# Sheet1.net
KiCad netlist of a schematic drawn in Altium Designer
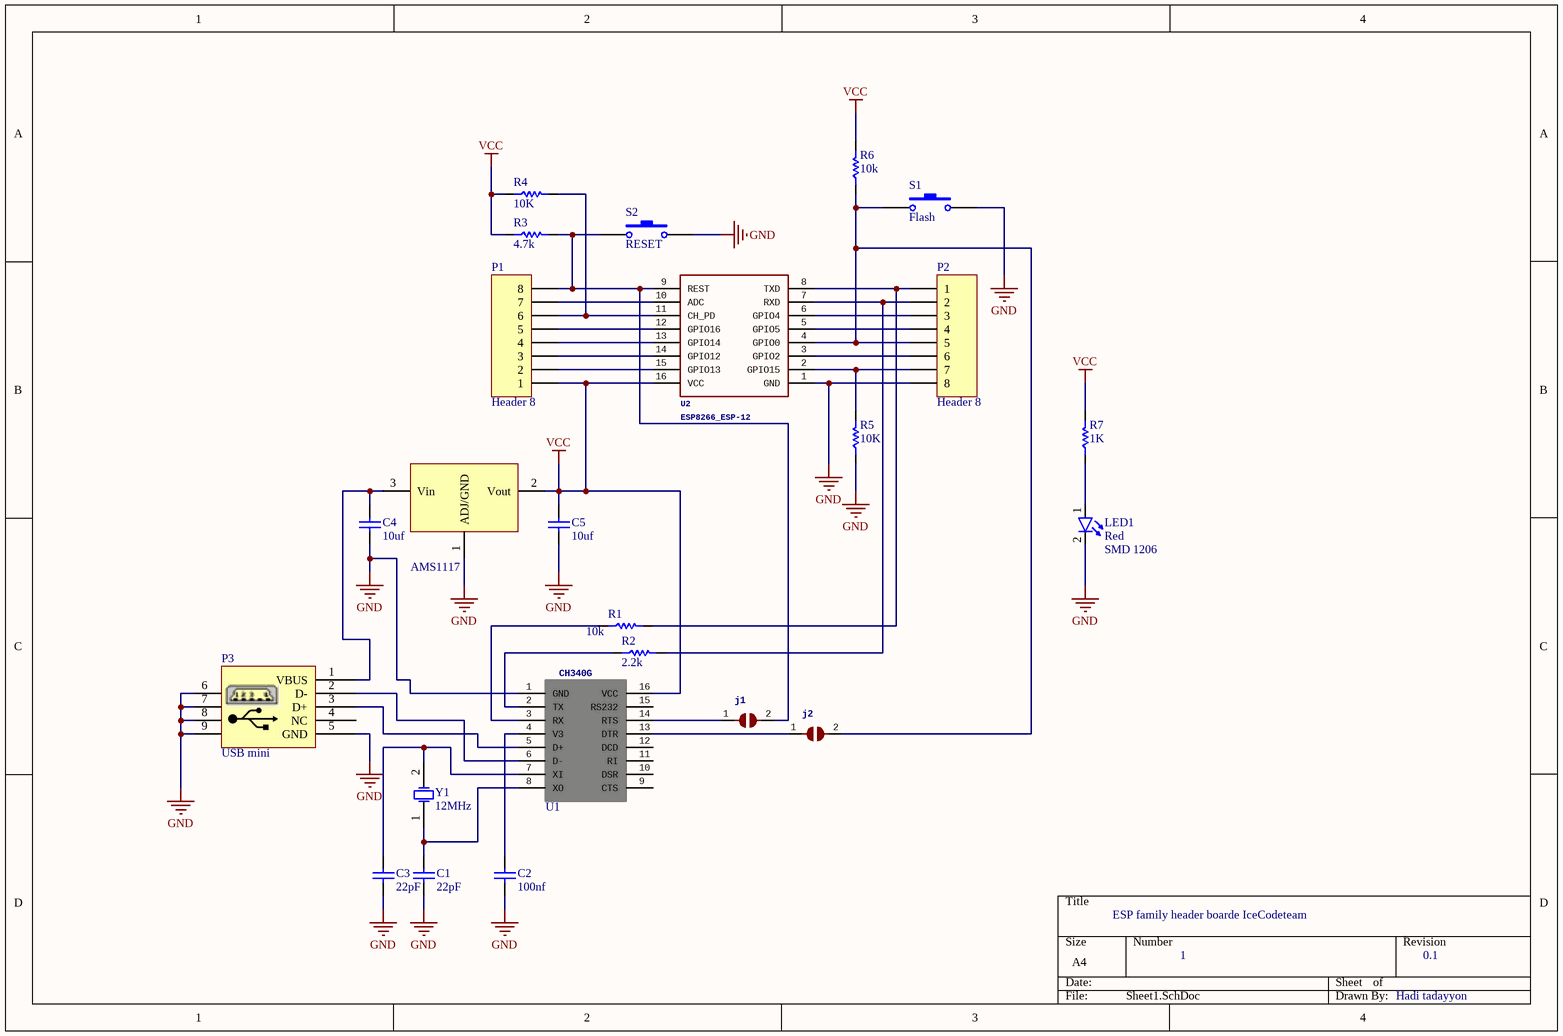
[diagram p0: Sheet1.SchDoc]

(export (version "E")
  (design (tool "Eeschema 10.0.6"))
  (components
    (comp (ref "AMS1117")
      (value "AMS1117")
      (footprint "SOT-223-3")
      (description "LDO 3.3V/5V/12V")
      (libsource (lib "ICs") (part "AMS1117"))
    )
    (comp (ref "C1")
      (value "22pF")
      (footprint "C1206")
      (description "Capacitor (Semiconductor SIM Model)")
      (fields (field (name "Comment") "Cap Semi") (field (name "PUBLISHER") "Altium Limited"))
      (libsource (lib "Miscellaneous Devices") (part "Cap Semi"))
    )
    (comp (ref "C2")
      (value "100nf")
      (footprint "C1206")
      (description "Capacitor (Semiconductor SIM Model)")
      (fields (field (name "Comment") "Cap Semi") (field (name "PUBLISHER") "Altium Limited"))
      (libsource (lib "Miscellaneous Devices") (part "Cap Semi"))
    )
    (comp (ref "C3")
      (value "22pF")
      (footprint "C1206")
      (description "Capacitor (Semiconductor SIM Model)")
      (fields (field (name "Comment") "Cap Semi") (field (name "PUBLISHER") "Altium Limited"))
      (libsource (lib "Miscellaneous Devices") (part "Cap Semi"))
    )
    (comp (ref "C4")
      (value "10uf")
      (footprint "C1206")
      (description "Capacitor (Semiconductor SIM Model)")
      (fields (field (name "Comment") "Cap Semi") (field (name "PUBLISHER") "Altium Limited"))
      (libsource (lib "Miscellaneous Devices") (part "Cap Semi"))
    )
    (comp (ref "C5")
      (value "10uf")
      (footprint "C1206")
      (description "Capacitor (Semiconductor SIM Model)")
      (fields (field (name "Comment") "Cap Semi") (field (name "PUBLISHER") "Altium Limited"))
      (libsource (lib "Miscellaneous Devices") (part "Cap Semi"))
    )
    (comp (ref "j1")
      (value "j1")
      (footprint "jmp")
      (description "SMD solder JUMPER")
      (libsource (lib "jumper") (part "SJ"))
    )
    (comp (ref "j2")
      (value "j1")
      (footprint "jmp")
      (description "SMD solder JUMPER")
      (libsource (lib "jumper") (part "SJ"))
    )
    (comp (ref "LED1")
      (value "Red")
      (footprint "LED SMD 1206")
      (description "LED")
      (fields
        (field (name "COLOR") "Red")
        (field (name "SIZE") "SMD 1206")
        (field (name "DESIGNER") "Saeid Jorablo")
      )
      (libsource (lib "Electrovolt Lib") (part "LED"))
    )
    (comp (ref "P1")
      (value "Header 8")
      (footprint "HDR1X8")
      (description "Header, 8-Pin")
      (fields (field (name "PUBLISHER") "Altium Limited"))
      (libsource (lib "") (part "Header 8_1"))
    )
    (comp (ref "P2")
      (value "Header 8")
      (footprint "HDR1X8")
      (description "Header, 8-Pin")
      (fields (field (name "PUBLISHER") "Altium Limited"))
      (libsource (lib "Miscellaneous Connectors") (part "Header 8"))
    )
    (comp (ref "P3")
      (value "USB mini")
      (footprint "microUSB")
      (description "mini USB Connector")
      (libsource (lib "Electrovolt Lib") (part "USB mini"))
    )
    (comp (ref "R1")
      (value "10k")
      (footprint "RES 1206 (3216X08L)")
      (description "Resistor")
      (fields (field (name "TOLERANCE") "5%") (field (name "POWER") "1/8 W"))
      (libsource (lib "Electrovolt Lib") (part "Resistor"))
    )
    (comp (ref "R2")
      (value "2.2k")
      (footprint "RES 1206 (3216X08L)")
      (description "Resistor")
      (fields (field (name "TOLERANCE") "5%") (field (name "POWER") "1/8 W"))
      (libsource (lib "Electrovolt Lib") (part "Resistor"))
    )
    (comp (ref "R3")
      (value "4.7k")
      (footprint "RES 1206 (3216X08L)")
      (description "Resistor")
      (fields (field (name "TOLERANCE") "5%") (field (name "POWER") "1/8 W"))
      (libsource (lib "Electrovolt Lib") (part "Resistor"))
    )
    (comp (ref "R4")
      (value "10K")
      (footprint "RES 1206 (3216X08L)")
      (description "Resistor")
      (fields (field (name "TOLERANCE") "5%") (field (name "POWER") "1/8 W"))
      (libsource (lib "Electrovolt Lib") (part "Resistor"))
    )
    (comp (ref "R5")
      (value "10K")
      (footprint "RES 1206 (3216X08L)")
      (description "Resistor")
      (fields (field (name "TOLERANCE") "5%") (field (name "POWER") "1/8 W"))
      (libsource (lib "Electrovolt Lib") (part "Resistor"))
    )
    (comp (ref "R6")
      (value "10k")
      (footprint "RES 1206 (3216X08L)")
      (description "Resistor")
      (fields (field (name "TOLERANCE") "5%") (field (name "POWER") "1/8 W"))
      (libsource (lib "Electrovolt Lib") (part "Resistor"))
    )
    (comp (ref "R7")
      (value "1K")
      (footprint "RES 1206 (3216X08L)")
      (description "Resistor")
      (fields (field (name "TOLERANCE") "5%") (field (name "POWER") "1/8 W"))
      (libsource (lib "Electrovolt Lib") (part "Resistor"))
    )
    (comp (ref "S1")
      (value "Flash")
      (footprint "3*6*2.5BTN")
      (description "Push Button Switch")
      (libsource (lib "Electrovolt Lib") (part "Switch PB"))
    )
    (comp (ref "S2")
      (value "RESET")
      (footprint "3*6*2.5BTN")
      (description "Push Button Switch")
      (libsource (lib "Electrovolt Lib") (part "Switch PB"))
    )
    (comp (ref "U1")
      (value "CH340G")
      (footprint "sop16")
      (fields (field (name "CH340G") "CH340G"))
      (libsource (lib "usb-serial") (part "CH340G"))
    )
    (comp (ref "U2")
      (value "ESP8266_ESP-12")
      (footprint "ESP-12s")
      (fields (field (name "ESP8266_ESP-12") "ESP8266_ESP-12"))
      (libsource (lib "ESP8266-ESP12") (part "ESP8266_ESP-12"))
    )
    (comp (ref "Y1")
      (value "12MHz")
      (footprint "Crystal SMD")
      (description "XTAL Crystal")
      (libsource (lib "Electrovolt Lib") (part "XTAL"))
    )
  )
  (nets
    (net (code "1") (name "GND") (class "Default")
      (node (ref "AMS1117") (pin "1") (pinfunction "ADJ/GND_1") (pintype "passive"))
      (node (ref "C1") (pin "1") (pinfunction "1_1") (pintype "passive"))
      (node (ref "C2") (pin "1") (pinfunction "1_1") (pintype "passive"))
      (node (ref "C3") (pin "1") (pinfunction "1_1") (pintype "passive"))
      (node (ref "C4") (pin "1") (pinfunction "1_1") (pintype "passive"))
      (node (ref "C5") (pin "1") (pinfunction "1_1") (pintype "passive"))
      (node (ref "LED1") (pin "2") (pinfunction "K_2") (pintype "passive"))
      (node (ref "P2") (pin "8") (pinfunction "8_8") (pintype "passive"))
      (node (ref "P3") (pin "5") (pinfunction "GND_5") (pintype "power_in"))
      (node (ref "P3") (pin "6") (pinfunction "6_6") (pintype "passive"))
      (node (ref "P3") (pin "7") (pinfunction "7_7") (pintype "passive"))
      (node (ref "P3") (pin "8") (pinfunction "8_8") (pintype "passive"))
      (node (ref "P3") (pin "9") (pinfunction "9_9") (pintype "passive"))
      (node (ref "R5") (pin "1") (pinfunction "1_1") (pintype "passive"))
      (node (ref "S1") (pin "2") (pinfunction "2_2") (pintype "passive"))
      (node (ref "S2") (pin "2") (pinfunction "2_2") (pintype "passive"))
      (node (ref "U1") (pin "1") (pinfunction "GND_1") (pintype "passive"))
      (node (ref "U2") (pin "1") (pinfunction "GND_1") (pintype "passive"))
    )
    (net (code "2") (name "Net-(AMS1117-Vin)") (class "Default")
      (node (ref "AMS1117") (pin "3") (pinfunction "Vin_3") (pintype "passive"))
      (node (ref "C4") (pin "2") (pinfunction "2_2") (pintype "passive"))
      (node (ref "P3") (pin "1") (pinfunction "VBUS_1") (pintype "power_in"))
    )
    (net (code "3") (name "Net-(LED1-A)") (class "Default")
      (node (ref "LED1") (pin "1") (pinfunction "A_1") (pintype "passive"))
      (node (ref "R7") (pin "1") (pinfunction "1_1") (pintype "passive"))
    )
    (net (code "4") (name "Net-(P3-D+)") (class "Default")
      (node (ref "P3") (pin "3") (pinfunction "D+_3") (pintype "passive"))
      (node (ref "U1") (pin "5") (pinfunction "D+_5") (pintype "passive"))
    )
    (net (code "5") (name "Net-(P3-D-)") (class "Default")
      (node (ref "P3") (pin "2") (pinfunction "D-_2") (pintype "passive"))
      (node (ref "U1") (pin "6") (pinfunction "D-_6") (pintype "passive"))
    )
    (net (code "6") (name "Net-(U1-DTR)") (class "Default")
      (node (ref "U1") (pin "13") (pinfunction "DTR_13") (pintype "passive"))
      (node (ref "j2") (pin "1") (pinfunction "1_1") (pintype "passive"))
    )
    (net (code "7") (name "Net-(U1-RTS)") (class "Default")
      (node (ref "U1") (pin "14") (pinfunction "RTS_14") (pintype "passive"))
      (node (ref "j1") (pin "1") (pinfunction "1_1") (pintype "passive"))
    )
    (net (code "8") (name "Net-(U1-RX)") (class "Default")
      (node (ref "R1") (pin "1") (pinfunction "1_1") (pintype "passive"))
      (node (ref "U1") (pin "3") (pinfunction "RX_3") (pintype "passive"))
    )
    (net (code "9") (name "Net-(U1-TX)") (class "Default")
      (node (ref "R2") (pin "1") (pinfunction "1_1") (pintype "passive"))
      (node (ref "U1") (pin "2") (pinfunction "TX_2") (pintype "passive"))
    )
    (net (code "10") (name "Net-(U1-V3)") (class "Default")
      (node (ref "C2") (pin "2") (pinfunction "2_2") (pintype "passive"))
      (node (ref "U1") (pin "4") (pinfunction "V3_4") (pintype "passive"))
    )
    (net (code "11") (name "Net-(U1-XI)") (class "Default")
      (node (ref "C3") (pin "2") (pinfunction "2_2") (pintype "passive"))
      (node (ref "U1") (pin "7") (pinfunction "XI_7") (pintype "passive"))
      (node (ref "Y1") (pin "2") (pinfunction "OSC2_2") (pintype "passive"))
    )
    (net (code "12") (name "Net-(U1-XO)") (class "Default")
      (node (ref "C1") (pin "2") (pinfunction "2_2") (pintype "passive"))
      (node (ref "U1") (pin "8") (pinfunction "XO_8") (pintype "passive"))
      (node (ref "Y1") (pin "1") (pinfunction "OSC1_1") (pintype "passive"))
    )
    (net (code "13") (name "Net-(U2-ADC)") (class "Default")
      (node (ref "P1") (pin "7") (pinfunction "7_7") (pintype "passive"))
      (node (ref "U2") (pin "10") (pinfunction "ADC_10") (pintype "passive"))
    )
    (net (code "14") (name "Net-(U2-CH_PD)") (class "Default")
      (node (ref "P1") (pin "6") (pinfunction "6_6") (pintype "passive"))
      (node (ref "R4") (pin "2") (pinfunction "2_2") (pintype "passive"))
      (node (ref "U2") (pin "11") (pinfunction "CH_PD_11") (pintype "passive"))
    )
    (net (code "15") (name "Net-(U2-GPIO0)") (class "Default")
      (node (ref "P2") (pin "5") (pinfunction "5_5") (pintype "passive"))
      (node (ref "R6") (pin "1") (pinfunction "1_1") (pintype "passive"))
      (node (ref "S1") (pin "1") (pinfunction "1_1") (pintype "passive"))
      (node (ref "U2") (pin "4") (pinfunction "GPIO0_4") (pintype "passive"))
      (node (ref "j2") (pin "2") (pinfunction "2_2") (pintype "passive"))
    )
    (net (code "16") (name "Net-(U2-GPIO2)") (class "Default")
      (node (ref "P2") (pin "6") (pinfunction "6_6") (pintype "passive"))
      (node (ref "U2") (pin "3") (pinfunction "GPIO2_3") (pintype "passive"))
    )
    (net (code "17") (name "Net-(U2-GPIO4)") (class "Default")
      (node (ref "P2") (pin "3") (pinfunction "3_3") (pintype "passive"))
      (node (ref "U2") (pin "6") (pinfunction "GPIO4_6") (pintype "passive"))
    )
    (net (code "18") (name "Net-(U2-GPIO5)") (class "Default")
      (node (ref "P2") (pin "4") (pinfunction "4_4") (pintype "passive"))
      (node (ref "U2") (pin "5") (pinfunction "GPIO5_5") (pintype "passive"))
    )
    (net (code "19") (name "Net-(U2-GPIO12)") (class "Default")
      (node (ref "P1") (pin "3") (pinfunction "3_3") (pintype "passive"))
      (node (ref "U2") (pin "14") (pinfunction "GPIO12_14") (pintype "passive"))
    )
    (net (code "20") (name "Net-(U2-GPIO13)") (class "Default")
      (node (ref "P1") (pin "2") (pinfunction "2_2") (pintype "passive"))
      (node (ref "U2") (pin "15") (pinfunction "GPIO13_15") (pintype "passive"))
    )
    (net (code "21") (name "Net-(U2-GPIO14)") (class "Default")
      (node (ref "P1") (pin "4") (pinfunction "4_4") (pintype "passive"))
      (node (ref "U2") (pin "13") (pinfunction "GPIO14_13") (pintype "passive"))
    )
    (net (code "22") (name "Net-(U2-GPIO15)") (class "Default")
      (node (ref "P2") (pin "7") (pinfunction "7_7") (pintype "passive"))
      (node (ref "R5") (pin "2") (pinfunction "2_2") (pintype "passive"))
      (node (ref "U2") (pin "2") (pinfunction "GPIO15_2") (pintype "passive"))
    )
    (net (code "23") (name "Net-(U2-GPIO16)") (class "Default")
      (node (ref "P1") (pin "5") (pinfunction "5_5") (pintype "passive"))
      (node (ref "U2") (pin "12") (pinfunction "GPIO16_12") (pintype "passive"))
    )
    (net (code "24") (name "Net-(U2-REST)") (class "Default")
      (node (ref "P1") (pin "8") (pinfunction "8_8") (pintype "passive"))
      (node (ref "R3") (pin "2") (pinfunction "2_2") (pintype "passive"))
      (node (ref "S2") (pin "1") (pinfunction "1_1") (pintype "passive"))
      (node (ref "U2") (pin "9") (pinfunction "REST_9") (pintype "passive"))
      (node (ref "j1") (pin "2") (pinfunction "2_2") (pintype "passive"))
    )
    (net (code "25") (name "Net-(U2-RXD)") (class "Default")
      (node (ref "P2") (pin "2") (pinfunction "2_2") (pintype "passive"))
      (node (ref "R2") (pin "2") (pinfunction "2_2") (pintype "passive"))
      (node (ref "U2") (pin "7") (pinfunction "RXD_7") (pintype "passive"))
    )
    (net (code "26") (name "Net-(U2-TXD)") (class "Default")
      (node (ref "P2") (pin "1") (pinfunction "1_1") (pintype "passive"))
      (node (ref "R1") (pin "2") (pinfunction "2_2") (pintype "passive"))
      (node (ref "U2") (pin "8") (pinfunction "TXD_8") (pintype "passive"))
    )
    (net (code "27") (name "VCC") (class "Default")
      (node (ref "AMS1117") (pin "2") (pinfunction "Vout_2") (pintype "passive"))
      (node (ref "C5") (pin "2") (pinfunction "2_2") (pintype "passive"))
      (node (ref "P1") (pin "1") (pinfunction "1_1") (pintype "passive"))
      (node (ref "R3") (pin "1") (pinfunction "1_1") (pintype "passive"))
      (node (ref "R4") (pin "1") (pinfunction "1_1") (pintype "passive"))
      (node (ref "R6") (pin "2") (pinfunction "2_2") (pintype "passive"))
      (node (ref "R7") (pin "2") (pinfunction "2_2") (pintype "passive"))
      (node (ref "U1") (pin "16") (pinfunction "VCC_16") (pintype "passive"))
      (node (ref "U2") (pin "16") (pinfunction "VCC_16") (pintype "passive"))
    )
    (net (code "28") (name "unconnected-(P3-NC-Pad4)") (class "Default")
      (node (ref "P3") (pin "4") (pinfunction "NC_4") (pintype "power_in"))
    )
    (net (code "29") (name "unconnected-(U1-CTS-Pad9)") (class "Default")
      (node (ref "U1") (pin "9") (pinfunction "CTS_9") (pintype "passive"))
    )
    (net (code "30") (name "unconnected-(U1-DCD-Pad12)") (class "Default")
      (node (ref "U1") (pin "12") (pinfunction "DCD_12") (pintype "passive"))
    )
    (net (code "31") (name "unconnected-(U1-DSR-Pad10)") (class "Default")
      (node (ref "U1") (pin "10") (pinfunction "DSR_10") (pintype "passive"))
    )
    (net (code "32") (name "unconnected-(U1-RI-Pad11)") (class "Default")
      (node (ref "U1") (pin "11") (pinfunction "RI_11") (pintype "passive"))
    )
    (net (code "33") (name "unconnected-(U1-RS232-Pad15)") (class "Default")
      (node (ref "U1") (pin "15") (pinfunction "RS232_15") (pintype "passive"))
    )
  )
)
